# SCHE.net
KiCad netlist of a schematic drawn in Altium Designer
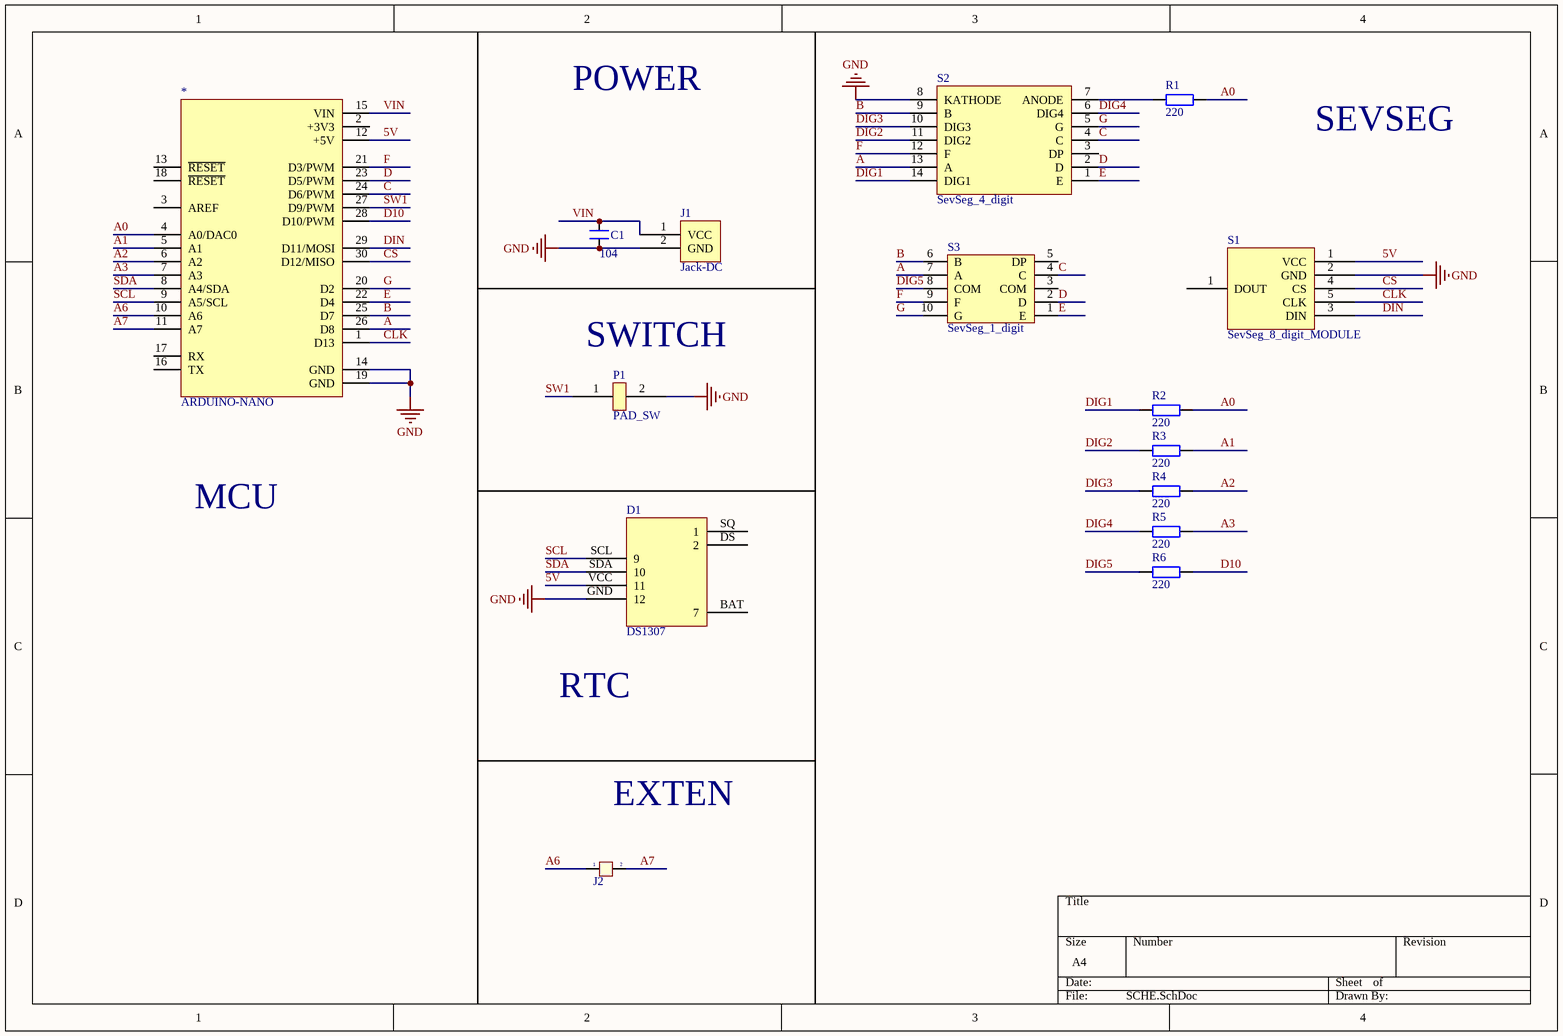
[diagram p0: SCHE.SchDoc]

(export (version "E")
  (design (tool "Eeschema 10.0.6"))
  (components
    (comp (ref "*")
      (value "ARDUINO-NANO")
      (footprint "ARDUINO-NANO")
      (libsource (lib "KHOEMACH_LIB") (part "ARDUINO-NANO"))
    )
    (comp (ref "C1")
      (value "104")
      (footprint "CN2")
      (description "Cap np 104 => 105pF")
      (libsource (lib "syhaunguyen") (part "CN2"))
    )
    (comp (ref "D1")
      (value "DS1307")
      (footprint "DS1307-MODULE")
      (libsource (lib "KHOEMACH_LIB") (part "DS1307_MODULE"))
    )
    (comp (ref "J1")
      (value "Jack-DC")
      (footprint "Jack-DC")
      (libsource (lib "KHOEMACH_LIB") (part "Jack-DC"))
    )
    (comp (ref "J2") (value "Jumper 2") (footprint "jp2h") (libsource (lib "syhaunguyen") (part "JP 2")))
    (comp (ref "P1") (value "PAD_SW") (footprint "PAD_SW") (libsource (lib "KHOEMACH_LIB") (part "PAD_SW")))
    (comp (ref "R1")
      (value "220")
      (footprint "R1/4W")
      (description "Resistor 1/4W")
      (libsource (lib "syhaunguyen") (part "R1/4W"))
    )
    (comp (ref "R2")
      (value "220")
      (footprint "R1/4W")
      (description "Resistor 1/4W")
      (libsource (lib "syhaunguyen") (part "R1/4W"))
    )
    (comp (ref "R3")
      (value "220")
      (footprint "R1/4W")
      (description "Resistor 1/4W")
      (libsource (lib "syhaunguyen") (part "R1/4W"))
    )
    (comp (ref "R4")
      (value "220")
      (footprint "R1/4W")
      (description "Resistor 1/4W")
      (libsource (lib "syhaunguyen") (part "R1/4W"))
    )
    (comp (ref "R5")
      (value "220")
      (footprint "R1/4W")
      (description "Resistor 1/4W")
      (libsource (lib "syhaunguyen") (part "R1/4W"))
    )
    (comp (ref "R6")
      (value "220")
      (footprint "R1/4W")
      (description "Resistor 1/4W")
      (libsource (lib "syhaunguyen") (part "R1/4W"))
    )
    (comp (ref "S1")
      (value "SevSeg_8_digit_MODULE")
      (footprint "SevSeg_8_digit_MODULE")
      (description "common kathode, MAX7219")
      (libsource (lib "KHOEMACH_LIB") (part "SevSeg_8_digit_MODULE"))
    )
    (comp (ref "S2")
      (value "SevSeg_4_digit")
      (footprint "SevSeg_4_digit")
      (description "common anode")
      (libsource (lib "KHOEMACH_LIB") (part "SevSeg_4_digit"))
    )
    (comp (ref "S3")
      (value "SevSeg_1_digit")
      (footprint "SevSeg_1_digit")
      (description "common anode")
      (libsource (lib "KHOEMACH_LIB") (part "SevSeg_1_digit"))
    )
  )
  (nets
    (net (code "1") (name "/5V") (class "Default")
      (node (ref "*") (pin "12") (pinfunction "+5V_12") (pintype "passive"))
      (node (ref "D1") (pin "VCC") (pinfunction "11_VCC") (pintype "passive"))
      (node (ref "S1") (pin "1") (pinfunction "VCC_1") (pintype "passive"))
    )
    (net (code "2") (name "/A") (class "Default")
      (node (ref "*") (pin "26") (pinfunction "D8_26") (pintype "passive"))
      (node (ref "S2") (pin "13") (pinfunction "A_13") (pintype "passive"))
      (node (ref "S3") (pin "7") (pinfunction "A_7") (pintype "passive"))
    )
    (net (code "3") (name "/A0") (class "Default")
      (node (ref "*") (pin "4") (pinfunction "A0/DAC0_4") (pintype "passive"))
      (node (ref "R1") (pin "2") (pinfunction "2_2") (pintype "passive"))
      (node (ref "R2") (pin "2") (pinfunction "2_2") (pintype "passive"))
    )
    (net (code "4") (name "/A1") (class "Default")
      (node (ref "*") (pin "5") (pinfunction "A1_5") (pintype "passive"))
      (node (ref "R3") (pin "2") (pinfunction "2_2") (pintype "passive"))
    )
    (net (code "5") (name "/A2") (class "Default")
      (node (ref "*") (pin "6") (pinfunction "A2_6") (pintype "passive"))
      (node (ref "R4") (pin "2") (pinfunction "2_2") (pintype "passive"))
    )
    (net (code "6") (name "/A3") (class "Default")
      (node (ref "*") (pin "7") (pinfunction "A3_7") (pintype "passive"))
      (node (ref "R5") (pin "2") (pinfunction "2_2") (pintype "passive"))
    )
    (net (code "7") (name "/A6") (class "Default")
      (node (ref "*") (pin "10") (pinfunction "A6_10") (pintype "passive"))
      (node (ref "J2") (pin "1") (pinfunction "1_1") (pintype "passive"))
    )
    (net (code "8") (name "/A7") (class "Default")
      (node (ref "*") (pin "11") (pinfunction "A7_11") (pintype "passive"))
      (node (ref "J2") (pin "2") (pinfunction "2_2") (pintype "passive"))
    )
    (net (code "9") (name "/B") (class "Default")
      (node (ref "*") (pin "25") (pinfunction "D7_25") (pintype "passive"))
      (node (ref "S2") (pin "9") (pinfunction "B_9") (pintype "passive"))
      (node (ref "S3") (pin "6") (pinfunction "B_6") (pintype "passive"))
    )
    (net (code "10") (name "/C") (class "Default")
      (node (ref "*") (pin "24") (pinfunction "D6/PWM_24") (pintype "passive"))
      (node (ref "S2") (pin "4") (pinfunction "C_4") (pintype "passive"))
      (node (ref "S3") (pin "4") (pinfunction "C_4") (pintype "passive"))
    )
    (net (code "11") (name "/CLK") (class "Default")
      (node (ref "*") (pin "1") (pinfunction "D13_1") (pintype "passive"))
      (node (ref "S1") (pin "5") (pinfunction "CLK_5") (pintype "passive"))
    )
    (net (code "12") (name "/CS") (class "Default")
      (node (ref "*") (pin "30") (pinfunction "D12/MISO_30") (pintype "passive"))
      (node (ref "S1") (pin "4") (pinfunction "CS_4") (pintype "passive"))
    )
    (net (code "13") (name "/D") (class "Default")
      (node (ref "*") (pin "23") (pinfunction "D5/PWM_23") (pintype "passive"))
      (node (ref "S2") (pin "2") (pinfunction "D_2") (pintype "passive"))
      (node (ref "S3") (pin "2") (pinfunction "D_2") (pintype "passive"))
    )
    (net (code "14") (name "/D10") (class "Default")
      (node (ref "*") (pin "28") (pinfunction "D10/PWM_28") (pintype "passive"))
      (node (ref "R6") (pin "2") (pinfunction "2_2") (pintype "passive"))
    )
    (net (code "15") (name "/DIG1") (class "Default")
      (node (ref "R2") (pin "1") (pinfunction "1_1") (pintype "passive"))
      (node (ref "S2") (pin "14") (pinfunction "DIG1_14") (pintype "passive"))
    )
    (net (code "16") (name "/DIG2") (class "Default")
      (node (ref "R3") (pin "1") (pinfunction "1_1") (pintype "passive"))
      (node (ref "S2") (pin "11") (pinfunction "DIG2_11") (pintype "passive"))
    )
    (net (code "17") (name "/DIG3") (class "Default")
      (node (ref "R4") (pin "1") (pinfunction "1_1") (pintype "passive"))
      (node (ref "S2") (pin "10") (pinfunction "DIG3_10") (pintype "passive"))
    )
    (net (code "18") (name "/DIG4") (class "Default")
      (node (ref "R5") (pin "1") (pinfunction "1_1") (pintype "passive"))
      (node (ref "S2") (pin "6") (pinfunction "DIG4_6") (pintype "passive"))
    )
    (net (code "19") (name "/DIG5") (class "Default")
      (node (ref "R6") (pin "1") (pinfunction "1_1") (pintype "passive"))
      (node (ref "S3") (pin "8") (pinfunction "COM_8") (pintype "passive"))
    )
    (net (code "20") (name "/DIN") (class "Default")
      (node (ref "*") (pin "29") (pinfunction "D11/MOSI_29") (pintype "passive"))
      (node (ref "S1") (pin "3") (pinfunction "DIN_3") (pintype "passive"))
    )
    (net (code "21") (name "/E") (class "Default")
      (node (ref "*") (pin "22") (pinfunction "D4_22") (pintype "passive"))
      (node (ref "S2") (pin "1") (pinfunction "E_1") (pintype "passive"))
      (node (ref "S3") (pin "1") (pinfunction "E_1") (pintype "passive"))
    )
    (net (code "22") (name "/F") (class "Default")
      (node (ref "*") (pin "21") (pinfunction "D3/PWM_21") (pintype "passive"))
      (node (ref "S2") (pin "12") (pinfunction "F_12") (pintype "passive"))
      (node (ref "S3") (pin "9") (pinfunction "F_9") (pintype "passive"))
    )
    (net (code "23") (name "/G") (class "Default")
      (node (ref "*") (pin "20") (pinfunction "D2_20") (pintype "passive"))
      (node (ref "S2") (pin "5") (pinfunction "G_5") (pintype "passive"))
      (node (ref "S3") (pin "10") (pinfunction "G_10") (pintype "passive"))
    )
    (net (code "24") (name "/SCL") (class "Default")
      (node (ref "*") (pin "9") (pinfunction "A5/SCL_9") (pintype "passive"))
      (node (ref "D1") (pin "SCL") (pinfunction "9_SCL") (pintype "passive"))
    )
    (net (code "25") (name "/SDA") (class "Default")
      (node (ref "*") (pin "8") (pinfunction "A4/SDA_8") (pintype "passive"))
      (node (ref "D1") (pin "SDA") (pinfunction "10_SDA") (pintype "passive"))
    )
    (net (code "26") (name "/SW1") (class "Default")
      (node (ref "*") (pin "27") (pinfunction "D9/PWM_27") (pintype "passive"))
      (node (ref "P1") (pin "1") (pinfunction "SW1_1") (pintype "passive"))
    )
    (net (code "27") (name "/VIN") (class "Default")
      (node (ref "*") (pin "15") (pinfunction "VIN_15") (pintype "passive"))
      (node (ref "C1") (pin "2") (pinfunction "2_2") (pintype "passive"))
      (node (ref "J1") (pin "1") (pinfunction "VCC_1") (pintype "passive"))
    )
    (net (code "28") (name "GND") (class "Default")
      (node (ref "*") (pin "14") (pinfunction "GND_14") (pintype "passive"))
      (node (ref "*") (pin "19") (pinfunction "GND_19") (pintype "passive"))
      (node (ref "C1") (pin "1") (pinfunction "1_1") (pintype "passive"))
      (node (ref "D1") (pin "GND") (pinfunction "12_GND") (pintype "passive"))
      (node (ref "J1") (pin "2") (pinfunction "GND_2") (pintype "passive"))
      (node (ref "P1") (pin "2") (pinfunction "SW2_2") (pintype "passive"))
      (node (ref "S1") (pin "2") (pinfunction "GND_2") (pintype "passive"))
      (node (ref "S2") (pin "8") (pinfunction "KATHODE_8") (pintype "passive"))
    )
    (net (code "29") (name "Net-(S2-ANODE)") (class "Default")
      (node (ref "R1") (pin "1") (pinfunction "1_1") (pintype "passive"))
      (node (ref "S2") (pin "7") (pinfunction "ANODE_7") (pintype "passive"))
    )
    (net (code "30") (name "unconnected-(*-+3V3-Pad2)") (class "Default")
      (node (ref "*") (pin "2") (pinfunction "+3V3_2") (pintype "passive"))
    )
    (net (code "31") (name "unconnected-(*-AREF-Pad3)") (class "Default")
      (node (ref "*") (pin "3") (pinfunction "AREF_3") (pintype "passive"))
    )
    (net (code "32") (name "unconnected-(*-RX-Pad17)") (class "Default")
      (node (ref "*") (pin "17") (pinfunction "RX_17") (pintype "passive"))
    )
    (net (code "33") (name "unconnected-(*-TX-Pad16)") (class "Default")
      (node (ref "*") (pin "16") (pinfunction "TX_16") (pintype "passive"))
    )
    (net (code "34") (name "unconnected-(*-~{RESET}-Pad13)") (class "Default")
      (node (ref "*") (pin "13") (pinfunction "~{RESET}_13") (pintype "passive"))
    )
    (net (code "35") (name "unconnected-(*-~{RESET}-Pad18)") (class "Default")
      (node (ref "*") (pin "18") (pinfunction "~{RESET}_18") (pintype "passive"))
    )
    (net (code "36") (name "unconnected-(D1-1-PadSQ)") (class "Default")
      (node (ref "D1") (pin "SQ") (pinfunction "1_SQ") (pintype "passive"))
    )
    (net (code "37") (name "unconnected-(D1-2-PadDS)") (class "Default")
      (node (ref "D1") (pin "DS") (pinfunction "2_DS") (pintype "passive"))
    )
    (net (code "38") (name "unconnected-(D1-7-PadBAT)") (class "Default")
      (node (ref "D1") (pin "BAT") (pinfunction "7_BAT") (pintype "passive"))
    )
    (net (code "39") (name "unconnected-(S1-DOUT-Pad1)") (class "Default")
      (node (ref "S1") (pin "1") (pinfunction "DOUT_1") (pintype "passive"))
    )
    (net (code "40") (name "unconnected-(S2-DP-Pad3)") (class "Default")
      (node (ref "S2") (pin "3") (pinfunction "DP_3") (pintype "passive"))
    )
    (net (code "41") (name "unconnected-(S3-COM-Pad3)") (class "Default")
      (node (ref "S3") (pin "3") (pinfunction "COM_3") (pintype "passive"))
    )
    (net (code "42") (name "unconnected-(S3-DP-Pad5)") (class "Default")
      (node (ref "S3") (pin "5") (pinfunction "DP_5") (pintype "passive"))
    )
  )
)
